# lcd.net
KiCad netlist of a schematic drawn in EAGLE
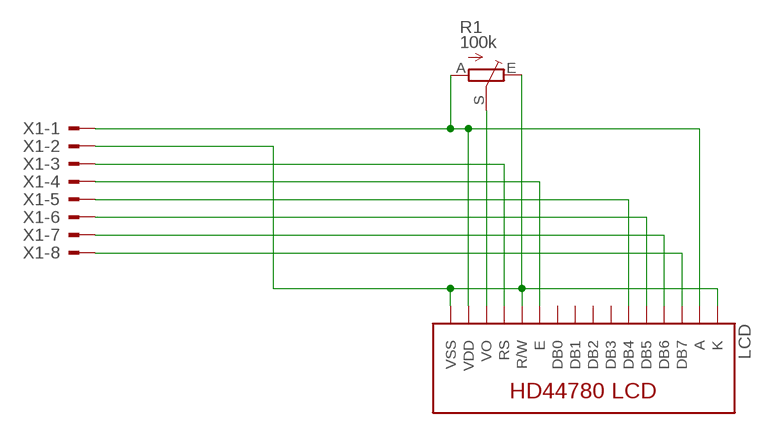
[diagram p0: schematic, sheet 1]

(export (version "E")
  (design (tool "Eeschema 10.0.6"))
  (components
    (comp (ref "LCD")
      (value "LCD-HD447804-HOLES16X2-4-HOLES")
      (footprint "eagle-import:LCD-16X2-4HOLES")
      (libsource (lib "eagle-import") (part "LCD-HD4478016X2-4-HOLES4-HOLES"))
    )
    (comp (ref "R1")
      (value "100k")
      (footprint "eagle-import:B25P")
      (libsource (lib "eagle-import") (part "TRIM_EU-B25P"))
    )
    (comp (ref "X1")
      (value "741256-49")
      (footprint "eagle-import:741256-49")
      (libsource (lib "eagle-import") (part "741256-49"))
    )
  )
  (nets
    (net (code "1") (name "Net-(LCD-A)") (class "Default")
      (node (ref "LCD") (pin "15") (pinfunction "A_15") (pintype "power_in"))
      (node (ref "LCD") (pin "2") (pinfunction "VDD_2") (pintype "power_in"))
      (node (ref "R1") (pin "A") (pinfunction "A_A") (pintype "passive"))
      (node (ref "X1") (pin "1") (pinfunction "KL_1") (pintype "passive"))
    )
    (net (code "2") (name "Net-(LCD-DB4)") (class "Default")
      (node (ref "LCD") (pin "11") (pinfunction "DB4_11") (pintype "bidirectional"))
      (node (ref "X1") (pin "5") (pinfunction "KL_5") (pintype "passive"))
    )
    (net (code "3") (name "Net-(LCD-DB5)") (class "Default")
      (node (ref "LCD") (pin "12") (pinfunction "DB5_12") (pintype "bidirectional"))
      (node (ref "X1") (pin "6") (pinfunction "KL_6") (pintype "passive"))
    )
    (net (code "4") (name "Net-(LCD-DB6)") (class "Default")
      (node (ref "LCD") (pin "13") (pinfunction "DB6_13") (pintype "bidirectional"))
      (node (ref "X1") (pin "7") (pinfunction "KL_7") (pintype "passive"))
    )
    (net (code "5") (name "Net-(LCD-DB7)") (class "Default")
      (node (ref "LCD") (pin "14") (pinfunction "DB7_14") (pintype "bidirectional"))
      (node (ref "X1") (pin "8") (pinfunction "KL_8") (pintype "passive"))
    )
    (net (code "6") (name "Net-(LCD-E)") (class "Default")
      (node (ref "LCD") (pin "6") (pinfunction "E_6") (pintype "input"))
      (node (ref "X1") (pin "4") (pinfunction "KL_4") (pintype "passive"))
    )
    (net (code "7") (name "Net-(LCD-K)") (class "Default")
      (node (ref "LCD") (pin "1") (pinfunction "VSS_1") (pintype "power_in"))
      (node (ref "LCD") (pin "16") (pinfunction "K_16") (pintype "power_in"))
      (node (ref "LCD") (pin "5") (pinfunction "R/W_5") (pintype "input"))
      (node (ref "R1") (pin "E") (pinfunction "E_E") (pintype "passive"))
      (node (ref "X1") (pin "2") (pinfunction "KL_2") (pintype "passive"))
    )
    (net (code "8") (name "Net-(LCD-RS)") (class "Default")
      (node (ref "LCD") (pin "4") (pinfunction "RS_4") (pintype "input"))
      (node (ref "X1") (pin "3") (pinfunction "KL_3") (pintype "passive"))
    )
    (net (code "9") (name "Net-(LCD-VO)") (class "Default")
      (node (ref "LCD") (pin "3") (pinfunction "VO_3") (pintype "bidirectional"))
      (node (ref "R1") (pin "S") (pinfunction "S_S") (pintype "passive"))
    )
    (net (code "10") (name "unconnected-(LCD-DB0-Pad7)") (class "Default")
      (node (ref "LCD") (pin "7") (pinfunction "DB0_7") (pintype "bidirectional"))
    )
    (net (code "11") (name "unconnected-(LCD-DB1-Pad8)") (class "Default")
      (node (ref "LCD") (pin "8") (pinfunction "DB1_8") (pintype "bidirectional"))
    )
    (net (code "12") (name "unconnected-(LCD-DB2-Pad9)") (class "Default")
      (node (ref "LCD") (pin "9") (pinfunction "DB2_9") (pintype "bidirectional"))
    )
    (net (code "13") (name "unconnected-(LCD-DB3-Pad10)") (class "Default")
      (node (ref "LCD") (pin "10") (pinfunction "DB3_10") (pintype "bidirectional"))
    )
  )
)
